# AD.net
KiCad netlist of a schematic drawn in Altium Designer
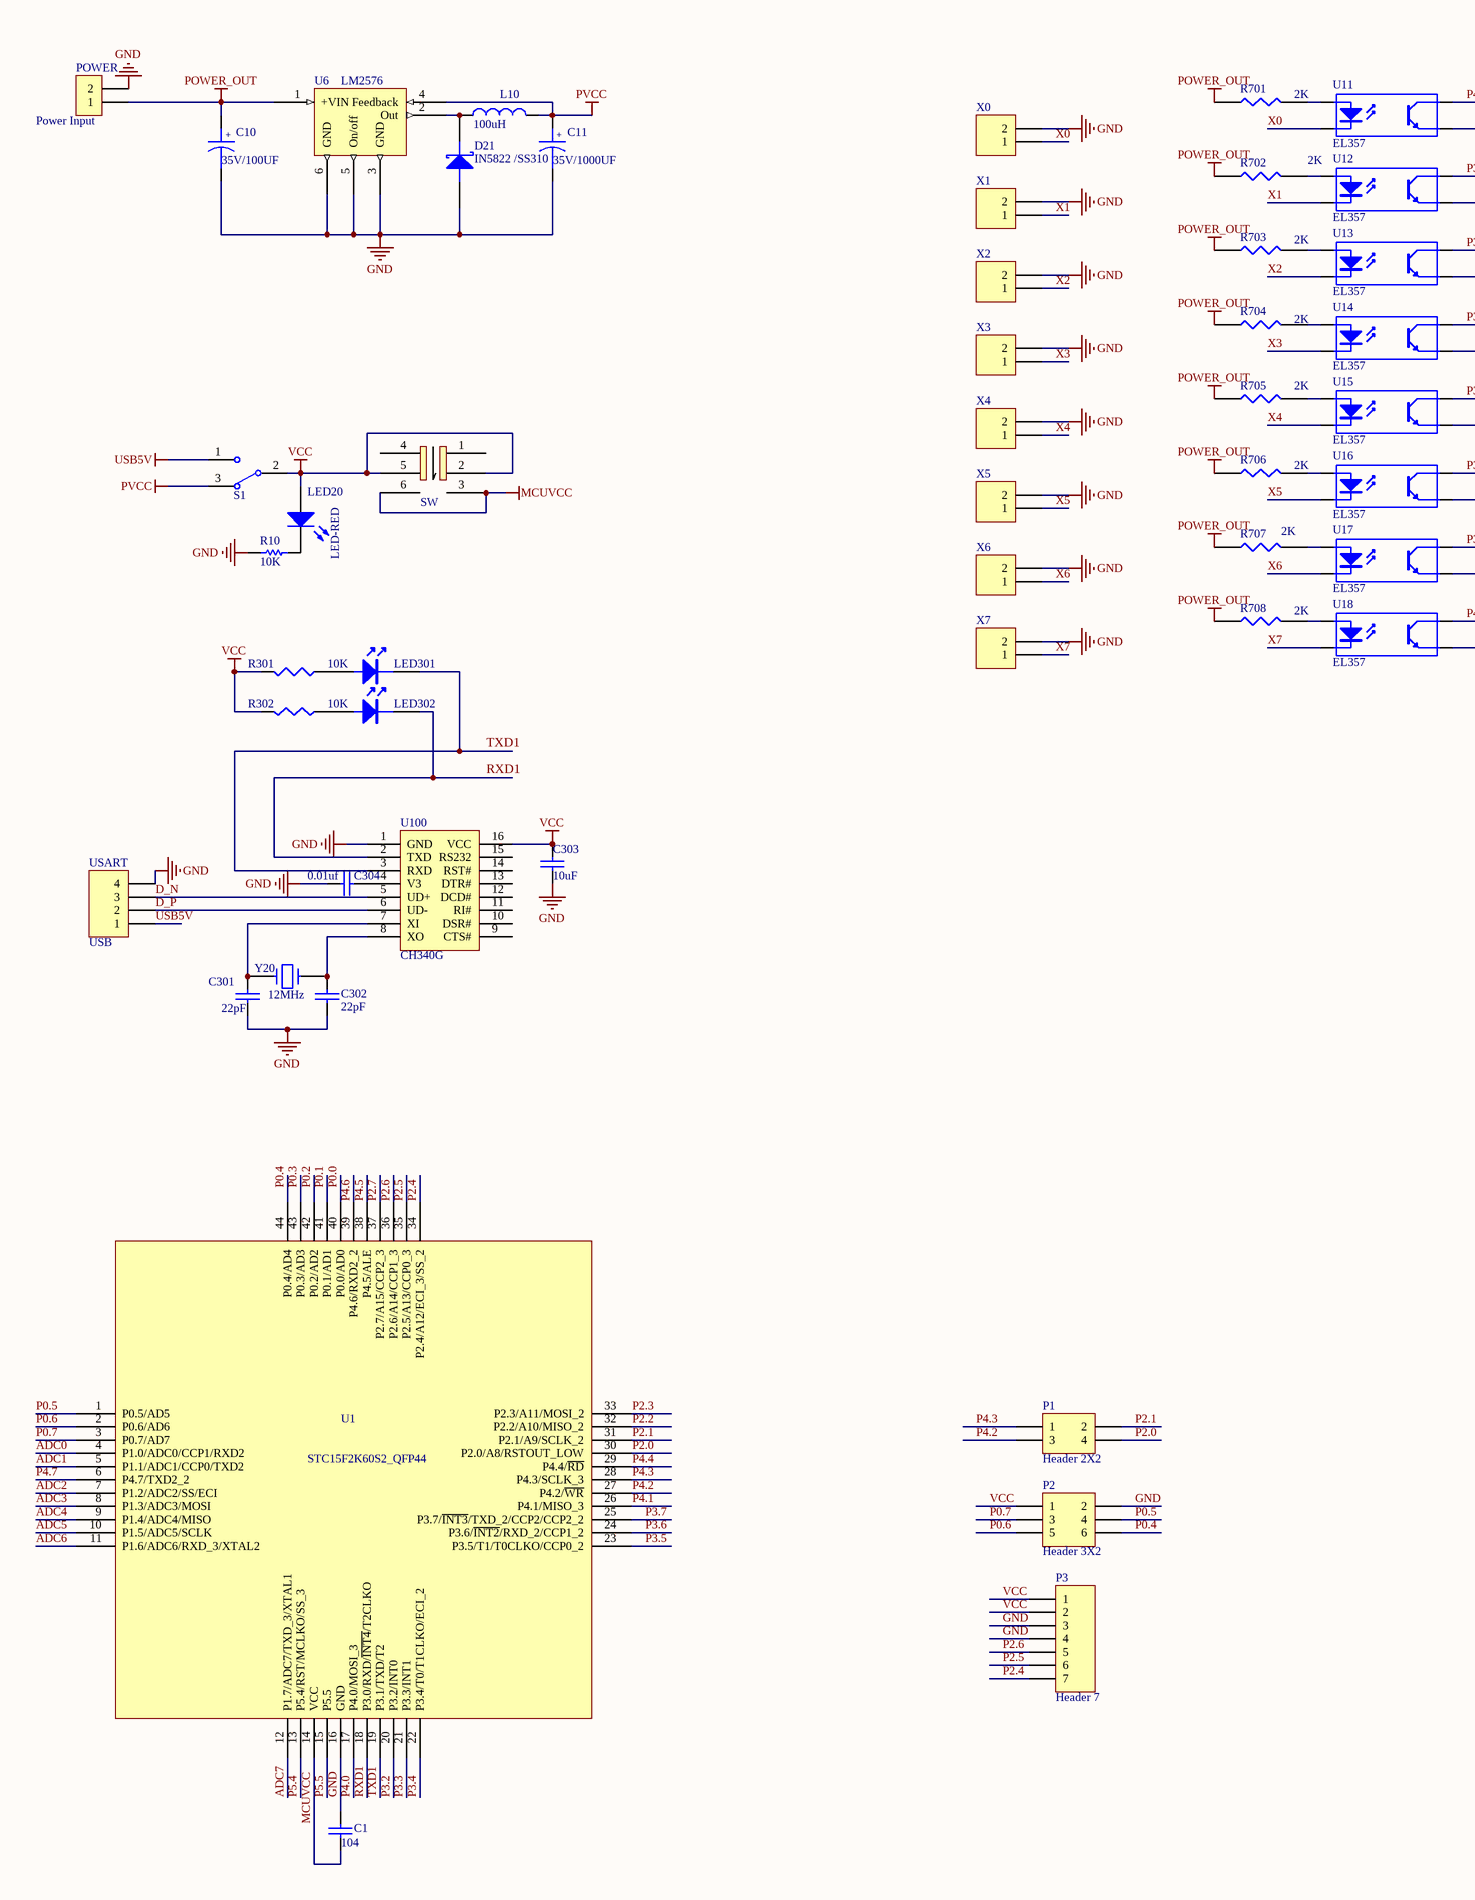
[diagram p0: AD.SchDoc, left]
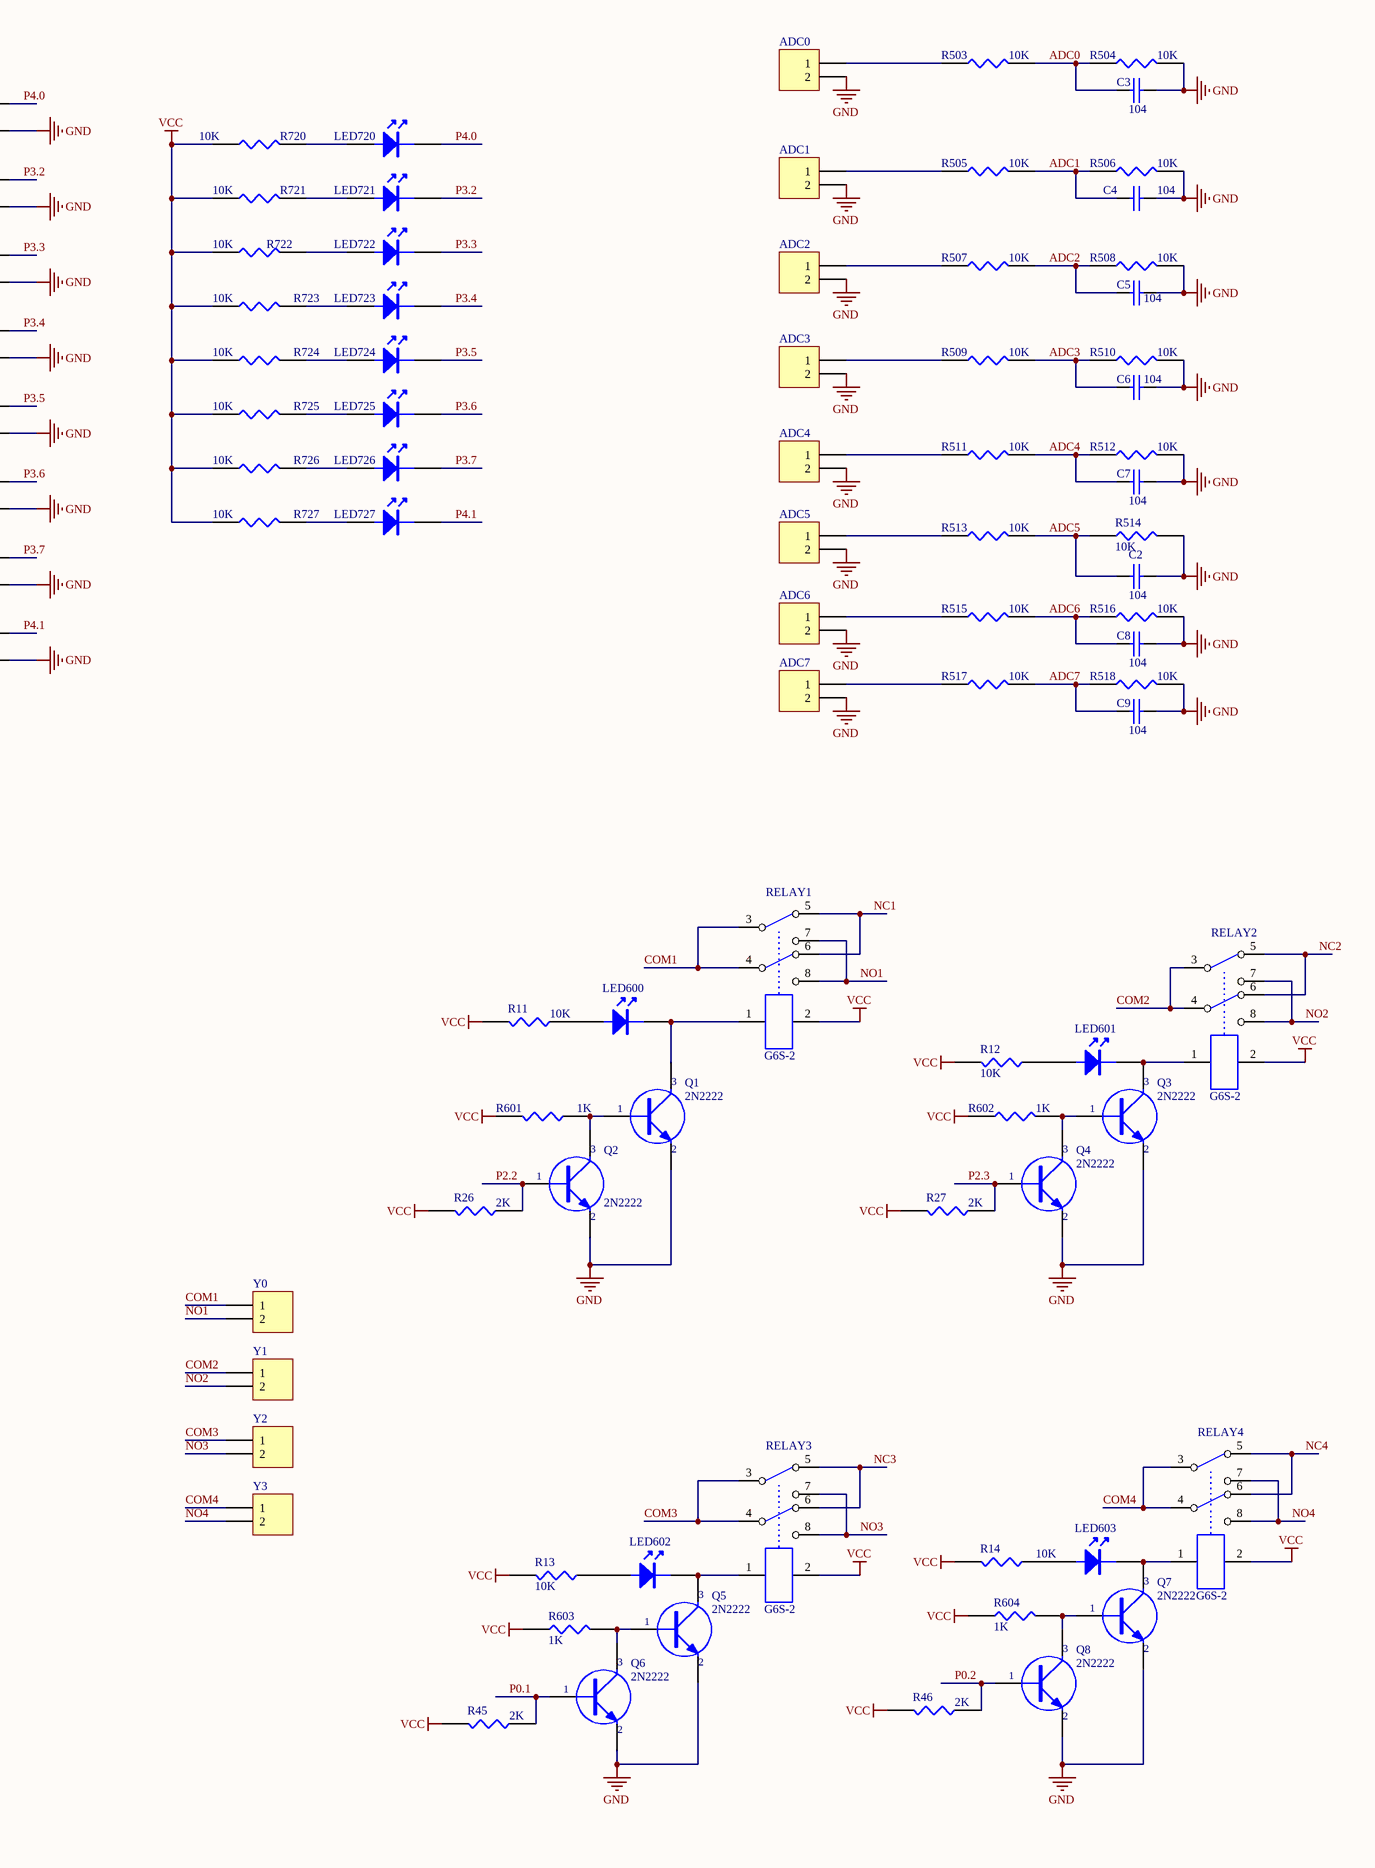
[diagram p1: AD.SchDoc, right]

(export (version "E")
  (design (tool "Eeschema 10.0.6"))
  (components
    (comp (ref "ADC0")
      (value "ADC")
      (footprint "CON2_1")
      (description "Header, 2-Pin")
      (fields (field (name "PUBLISHER") "Altium Limited"))
      (libsource (lib "") (part "Header 2_1"))
    )
    (comp (ref "ADC1")
      (value "ADC")
      (footprint "CON2_1")
      (description "Header, 2-Pin")
      (fields (field (name "PUBLISHER") "Altium Limited"))
      (libsource (lib "") (part "Header 2_1"))
    )
    (comp (ref "ADC2")
      (value "ADC")
      (footprint "CON2_1")
      (description "Header, 2-Pin")
      (fields (field (name "PUBLISHER") "Altium Limited"))
      (libsource (lib "") (part "Header 2_1"))
    )
    (comp (ref "ADC3")
      (value "ADC")
      (footprint "CON2_1")
      (description "Header, 2-Pin")
      (fields (field (name "PUBLISHER") "Altium Limited"))
      (libsource (lib "") (part "Header 2_1"))
    )
    (comp (ref "ADC4")
      (value "ADC")
      (footprint "CON2_1")
      (description "Header, 2-Pin")
      (fields (field (name "PUBLISHER") "Altium Limited"))
      (libsource (lib "") (part "Header 2_1"))
    )
    (comp (ref "ADC5")
      (value "ADC")
      (footprint "CON2_1")
      (description "Header, 2-Pin")
      (fields (field (name "PUBLISHER") "Altium Limited"))
      (libsource (lib "") (part "Header 2_1"))
    )
    (comp (ref "ADC6")
      (value "ADC")
      (footprint "CON2_1")
      (description "Header, 2-Pin")
      (fields (field (name "PUBLISHER") "Altium Limited"))
      (libsource (lib "") (part "Header 2_1"))
    )
    (comp (ref "ADC7")
      (value "ADC")
      (footprint "CON2_1")
      (description "Header, 2-Pin")
      (fields (field (name "PUBLISHER") "Altium Limited"))
      (libsource (lib "") (part "Header 2_1"))
    )
    (comp (ref "C1") (value "104") (footprint "C-0805") (libsource (lib "brante_zhou") (part "CAP1")))
    (comp (ref "C2") (value "104") (footprint "C-0805") (libsource (lib "brante_zhou") (part "CAP1")))
    (comp (ref "C3") (value "104") (footprint "C-0805") (libsource (lib "brante_zhou") (part "CAP1")))
    (comp (ref "C4") (value "104") (footprint "C-0805") (libsource (lib "brante_zhou") (part "CAP1")))
    (comp (ref "C5") (value "104") (footprint "C-0805") (libsource (lib "brante_zhou") (part "CAP1")))
    (comp (ref "C6") (value "104") (footprint "C-0805") (libsource (lib "brante_zhou") (part "CAP1")))
    (comp (ref "C7") (value "104") (footprint "C-0805") (libsource (lib "brante_zhou") (part "CAP1")))
    (comp (ref "C8") (value "104") (footprint "C-0805") (libsource (lib "brante_zhou") (part "CAP1")))
    (comp (ref "C9") (value "104") (footprint "C-0805") (libsource (lib "brante_zhou") (part "CAP1")))
    (comp (ref "C10") (value "35V/100UF") (footprint "RB") (libsource (lib "My_Schlib") (part "CAP2")))
    (comp (ref "C11") (value "35V/1000UF") (footprint "L-DIP") (libsource (lib "My_Schlib") (part "CAP2")))
    (comp (ref "C301") (value "22pF") (footprint "C-0805") (libsource (lib "My_Schlib") (part "CAP1")))
    (comp (ref "C302") (value "22pF") (footprint "C-0805") (libsource (lib "My_Schlib") (part "CAP1")))
    (comp (ref "C303") (value "10uF") (footprint "C-0805") (libsource (lib "My_Schlib") (part "CAP1")))
    (comp (ref "C304") (value "0.01uf") (footprint "C-0603") (libsource (lib "My_Schlib") (part "CAP1")))
    (comp (ref "D21")
      (value "IN5822 /SS310")
      (footprint "DO-214AC")
      (description "Schottky Diode")
      (libsource (lib "Miscellaneous Devices") (part "DIODE SCHOTTKY"))
    )
    (comp (ref "L10")
      (value "100uH")
      (footprint "L-DIP")
      (description "Inductor")
      (fields (field (name "PUBLISHER") "Altium Limited"))
      (libsource (lib "Miscellaneous Devices") (part "Inductor"))
    )
    (comp (ref "LED20")
      (value "LED-RED")
      (footprint "led-0805")
      (description "Typical INFRARED GaAs LED")
      (fields (field (name "PUBLISHER") "Altium Limited"))
      (libsource (lib "Miscellaneous Devices") (part "LED0"))
    )
    (comp (ref "LED301") (value "~") (footprint "LED-0805") (libsource (lib "*") (part "LED")))
    (comp (ref "LED302") (value "~") (footprint "LED-0805") (libsource (lib "*") (part "LED")))
    (comp (ref "LED600") (value "~") (footprint "LED-0805") (libsource (lib "brante_zhou") (part "LED")))
    (comp (ref "LED601") (value "~") (footprint "LED-0805") (libsource (lib "brante_zhou") (part "LED")))
    (comp (ref "LED602") (value "~") (footprint "LED-0805") (libsource (lib "brante_zhou") (part "LED")))
    (comp (ref "LED603") (value "~") (footprint "LED-0805") (libsource (lib "brante_zhou") (part "LED")))
    (comp (ref "LED720") (value "LED") (footprint "LED-0805") (libsource (lib "brante_zhou") (part "LED")))
    (comp (ref "LED721") (value "LED") (footprint "LED-0805") (libsource (lib "brante_zhou") (part "LED")))
    (comp (ref "LED722") (value "LED") (footprint "LED-0805") (libsource (lib "brante_zhou") (part "LED")))
    (comp (ref "LED723") (value "LED") (footprint "LED-0805") (libsource (lib "brante_zhou") (part "LED")))
    (comp (ref "LED724") (value "LED") (footprint "LED-0805") (libsource (lib "brante_zhou") (part "LED")))
    (comp (ref "LED725") (value "LED") (footprint "LED-0805") (libsource (lib "brante_zhou") (part "LED")))
    (comp (ref "LED726") (value "LED") (footprint "LED-0805") (libsource (lib "brante_zhou") (part "LED")))
    (comp (ref "LED727") (value "LED") (footprint "LED-0805") (libsource (lib "brante_zhou") (part "LED")))
    (comp (ref "P1")
      (value "Header 2X2")
      (footprint "HDR2X2")
      (description "Header, 2-Pin, Dual row")
      (fields (field (name "PUBLISHER") "Altium Limited"))
      (libsource (lib "Miscellaneous Connectors") (part "Header 2X2"))
    )
    (comp (ref "P2")
      (value "Header 3X2")
      (footprint "HDR2X3")
      (description "Header, 3-Pin, Dual row")
      (fields (field (name "PUBLISHER") "Altium Limited"))
      (libsource (lib "Miscellaneous Connectors") (part "Header 3X2"))
    )
    (comp (ref "P3")
      (value "Header 7")
      (footprint "HDR1X7")
      (description "Header, 7-Pin")
      (fields (field (name "PUBLISHER") "Altium Limited"))
      (libsource (lib "Miscellaneous Connectors") (part "Header 7"))
    )
    (comp (ref "POWER")
      (value "Power Input")
      (footprint "CON2_1")
      (libsource (lib "brante_zhou") (part "CON2"))
    )
    (comp (ref "Q1")
      (value "2N2222")
      (footprint "SOT23A")
      (description "NPN Transistor")
      (libsource (lib "My_Schlib") (part "NPN_S8050"))
    )
    (comp (ref "Q2")
      (value "2N2222")
      (footprint "SOT23A")
      (description "NPN Transistor")
      (libsource (lib "My_Schlib") (part "NPN_S8050"))
    )
    (comp (ref "Q3")
      (value "2N2222")
      (footprint "SOT23A")
      (description "NPN Transistor")
      (libsource (lib "My_Schlib") (part "NPN_S8050"))
    )
    (comp (ref "Q4")
      (value "2N2222")
      (footprint "SOT23A")
      (description "NPN Transistor")
      (libsource (lib "My_Schlib") (part "NPN_S8050"))
    )
    (comp (ref "Q5")
      (value "2N2222")
      (footprint "SOT23A")
      (description "NPN Transistor")
      (libsource (lib "My_Schlib") (part "NPN_S8050"))
    )
    (comp (ref "Q6")
      (value "2N2222")
      (footprint "SOT23A")
      (description "NPN Transistor")
      (libsource (lib "My_Schlib") (part "NPN_S8050"))
    )
    (comp (ref "Q7")
      (value "2N2222")
      (footprint "SOT23A")
      (description "NPN Transistor")
      (libsource (lib "My_Schlib") (part "NPN_S8050"))
    )
    (comp (ref "Q8")
      (value "2N2222")
      (footprint "SOT23A")
      (description "NPN Transistor")
      (libsource (lib "My_Schlib") (part "NPN_S8050"))
    )
    (comp (ref "R10")
      (value "10K")
      (footprint "R0805")
      (description "Semiconductor Resistor")
      (fields (field (name "PUBLISHER") "Altium Limited"))
      (libsource (lib "Miscellaneous Devices") (part "Res Semi"))
    )
    (comp (ref "R11") (value "10K") (footprint "R0805") (libsource (lib "brante_zhou") (part "RES")))
    (comp (ref "R12") (value "10K") (footprint "R0805") (libsource (lib "brante_zhou") (part "RES")))
    (comp (ref "R13") (value "10K") (footprint "R0805") (libsource (lib "brante_zhou") (part "RES")))
    (comp (ref "R14") (value "10K") (footprint "R0805") (libsource (lib "brante_zhou") (part "RES")))
    (comp (ref "R26") (value "2K") (footprint "R0805") (libsource (lib "brante_zhou") (part "RES")))
    (comp (ref "R27") (value "2K") (footprint "R0805") (libsource (lib "brante_zhou") (part "RES")))
    (comp (ref "R45") (value "2K") (footprint "R0805") (libsource (lib "brante_zhou") (part "RES")))
    (comp (ref "R46") (value "2K") (footprint "R0805") (libsource (lib "brante_zhou") (part "RES")))
    (comp (ref "R301")
      (value "10K")
      (footprint "R0805")
      (description "Resistor")
      (fields (field (name "PUBLISHER") "Altium Limited"))
      (libsource (lib "Miscellaneous Devices") (part "Res3"))
    )
    (comp (ref "R302")
      (value "10K")
      (footprint "R0805")
      (description "Resistor")
      (fields (field (name "PUBLISHER") "Altium Limited"))
      (libsource (lib "Miscellaneous Devices") (part "Res3"))
    )
    (comp (ref "R503") (value "10K") (footprint "R0805") (libsource (lib "brante_zhou") (part "RES")))
    (comp (ref "R504") (value "10K") (footprint "R0805") (libsource (lib "brante_zhou") (part "RES")))
    (comp (ref "R505") (value "10K") (footprint "R0805") (libsource (lib "brante_zhou") (part "RES")))
    (comp (ref "R506") (value "10K") (footprint "R0805") (libsource (lib "brante_zhou") (part "RES")))
    (comp (ref "R507") (value "10K") (footprint "R0805") (libsource (lib "brante_zhou") (part "RES")))
    (comp (ref "R508") (value "10K") (footprint "R0805") (libsource (lib "brante_zhou") (part "RES")))
    (comp (ref "R509") (value "10K") (footprint "R0805") (libsource (lib "brante_zhou") (part "RES")))
    (comp (ref "R510") (value "10K") (footprint "R0805") (libsource (lib "brante_zhou") (part "RES")))
    (comp (ref "R511") (value "10K") (footprint "R0805") (libsource (lib "brante_zhou") (part "RES")))
    (comp (ref "R512") (value "10K") (footprint "R0805") (libsource (lib "brante_zhou") (part "RES")))
    (comp (ref "R513") (value "10K") (footprint "R0805") (libsource (lib "brante_zhou") (part "RES")))
    (comp (ref "R514") (value "10K") (footprint "R0805") (libsource (lib "brante_zhou") (part "RES")))
    (comp (ref "R515") (value "10K") (footprint "R0805") (libsource (lib "brante_zhou") (part "RES")))
    (comp (ref "R516") (value "10K") (footprint "R0805") (libsource (lib "brante_zhou") (part "RES")))
    (comp (ref "R517") (value "10K") (footprint "R0805") (libsource (lib "brante_zhou") (part "RES")))
    (comp (ref "R518") (value "10K") (footprint "R0805") (libsource (lib "brante_zhou") (part "RES")))
    (comp (ref "R601") (value "1K") (footprint "R0805") (libsource (lib "brante_zhou") (part "RES")))
    (comp (ref "R602") (value "1K") (footprint "R0805") (libsource (lib "brante_zhou") (part "RES")))
    (comp (ref "R603") (value "1K") (footprint "R0805") (libsource (lib "brante_zhou") (part "RES")))
    (comp (ref "R604") (value "1K") (footprint "R0805") (libsource (lib "brante_zhou") (part "RES")))
    (comp (ref "R701") (value "2K") (footprint "R0805") (libsource (lib "brante_zhou") (part "RES")))
    (comp (ref "R702") (value "2K") (footprint "R0805") (libsource (lib "brante_zhou") (part "RES")))
    (comp (ref "R703") (value "2K") (footprint "R0805") (libsource (lib "brante_zhou") (part "RES")))
    (comp (ref "R704") (value "2K") (footprint "R0805") (libsource (lib "brante_zhou") (part "RES")))
    (comp (ref "R705") (value "2K") (footprint "R0805") (libsource (lib "brante_zhou") (part "RES")))
    (comp (ref "R706") (value "2K") (footprint "R0805") (libsource (lib "brante_zhou") (part "RES")))
    (comp (ref "R707") (value "2K") (footprint "R0805") (libsource (lib "brante_zhou") (part "RES")))
    (comp (ref "R708") (value "2K") (footprint "R0805") (libsource (lib "brante_zhou") (part "RES")))
    (comp (ref "R720") (value "10K") (footprint "R0805") (libsource (lib "brante_zhou") (part "RES")))
    (comp (ref "R721") (value "10K") (footprint "R0805") (libsource (lib "brante_zhou") (part "RES")))
    (comp (ref "R722") (value "10K") (footprint "R0805") (libsource (lib "brante_zhou") (part "RES")))
    (comp (ref "R723") (value "10K") (footprint "R0805") (libsource (lib "brante_zhou") (part "RES")))
    (comp (ref "R724") (value "10K") (footprint "R0805") (libsource (lib "brante_zhou") (part "RES")))
    (comp (ref "R725") (value "10K") (footprint "R0805") (libsource (lib "brante_zhou") (part "RES")))
    (comp (ref "R726") (value "10K") (footprint "R0805") (libsource (lib "brante_zhou") (part "RES")))
    (comp (ref "R727") (value "10K") (footprint "R0805") (libsource (lib "brante_zhou") (part "RES")))
    (comp (ref "RELAY1")
      (value "G6S-2")
      (footprint "G6S-2")
      (libsource (lib "My_Schlib") (part "RELAY-G6S-2"))
    )
    (comp (ref "RELAY2")
      (value "G6S-2")
      (footprint "G6S-2")
      (libsource (lib "My_Schlib") (part "RELAY-G6S-2"))
    )
    (comp (ref "RELAY3")
      (value "G6S-2")
      (footprint "G6S-2")
      (libsource (lib "My_Schlib") (part "RELAY-G6S-2"))
    )
    (comp (ref "RELAY4")
      (value "G6S-2")
      (footprint "G6S-2")
      (libsource (lib "My_Schlib") (part "RELAY-G6S-2"))
    )
    (comp (ref "S1")
      (value "SW-SPDT_2")
      (footprint "SW_1")
      (description "SPDT Subminiature Toggle Switch, Right Angle Mounting, Vertical Actuation")
      (fields (field (name "PUBLISHER") "Altium Limited"))
      (libsource (lib "My_Schlib") (part "SW-SPDT_2"))
    )
    (comp (ref "SW") (value "SW") (footprint "SW") (libsource (lib "RelayBoard") (part "SW")))
    (comp (ref "U1")
      (value "STC15F2K60S2_QFP44")
      (footprint "PQFP44")
      (libsource (lib "stcmcu_altium_lib") (part "STC15F2K60S2_QFP44"))
    )
    (comp (ref "U6") (value "LM2576") (footprint "LM2576") (libsource (lib "My_Schlib") (part "LM2576")))
    (comp (ref "U11")
      (value "EL357")
      (footprint "el357")
      (description "4-Pin Phototransistor Optocoupler")
      (fields (field (name "PUBLISHER") "Altium Limited"))
      (libsource (lib "My_Schlib") (part "Optoisolator"))
    )
    (comp (ref "U12")
      (value "EL357")
      (footprint "EL357")
      (description "4-Pin Phototransistor Optocoupler")
      (fields (field (name "PUBLISHER") "Altium Limited"))
      (libsource (lib "My_Schlib") (part "Optoisolator"))
    )
    (comp (ref "U13")
      (value "EL357")
      (footprint "EL357")
      (description "4-Pin Phototransistor Optocoupler")
      (fields (field (name "PUBLISHER") "Altium Limited"))
      (libsource (lib "My_Schlib") (part "Optoisolator"))
    )
    (comp (ref "U14")
      (value "EL357")
      (footprint "EL357")
      (description "4-Pin Phototransistor Optocoupler")
      (fields (field (name "PUBLISHER") "Altium Limited"))
      (libsource (lib "My_Schlib") (part "Optoisolator"))
    )
    (comp (ref "U15")
      (value "EL357")
      (footprint "EL357")
      (description "4-Pin Phototransistor Optocoupler")
      (fields (field (name "PUBLISHER") "Altium Limited"))
      (libsource (lib "My_Schlib") (part "Optoisolator"))
    )
    (comp (ref "U16")
      (value "EL357")
      (footprint "EL357")
      (description "4-Pin Phototransistor Optocoupler")
      (fields (field (name "PUBLISHER") "Altium Limited"))
      (libsource (lib "My_Schlib") (part "Optoisolator"))
    )
    (comp (ref "U17")
      (value "EL357")
      (footprint "EL357")
      (description "4-Pin Phototransistor Optocoupler")
      (fields (field (name "PUBLISHER") "Altium Limited"))
      (libsource (lib "My_Schlib") (part "Optoisolator"))
    )
    (comp (ref "U18")
      (value "EL357")
      (footprint "EL357")
      (description "4-Pin Phototransistor Optocoupler")
      (fields (field (name "PUBLISHER") "Altium Limited"))
      (libsource (lib "My_Schlib") (part "Optoisolator"))
    )
    (comp (ref "U100") (value "CH340G") (footprint "CH340G") (libsource (lib "My_Schlib") (part "CH340G")))
    (comp (ref "USART")
      (value "USB")
      (footprint "USB2.0_A")
      (description "Header, 4-Pin")
      (fields (field (name "PUBLISHER") "Altium Limited"))
      (libsource (lib "Miscellaneous Connectors") (part "Header 4"))
    )
    (comp (ref "X0")
      (value "XH2.54")
      (footprint "con2_1")
      (description "Header, 2-Pin")
      (fields (field (name "PUBLISHER") "Altium Limited"))
      (libsource (lib "") (part "Header 2_2"))
    )
    (comp (ref "X1")
      (value "XH2.54")
      (footprint "con2_1")
      (description "Header, 2-Pin")
      (fields (field (name "PUBLISHER") "Altium Limited"))
      (libsource (lib "") (part "Header 2_2"))
    )
    (comp (ref "X2")
      (value "XH2.54")
      (footprint "con2_1")
      (description "Header, 2-Pin")
      (fields (field (name "PUBLISHER") "Altium Limited"))
      (libsource (lib "") (part "Header 2_2"))
    )
    (comp (ref "X3")
      (value "XH2.54")
      (footprint "con2_1")
      (description "Header, 2-Pin")
      (fields (field (name "PUBLISHER") "Altium Limited"))
      (libsource (lib "") (part "Header 2_2"))
    )
    (comp (ref "X4")
      (value "XH2.54")
      (footprint "con2_1")
      (description "Header, 2-Pin")
      (fields (field (name "PUBLISHER") "Altium Limited"))
      (libsource (lib "") (part "Header 2_2"))
    )
    (comp (ref "X5")
      (value "XH2.54")
      (footprint "con2_1")
      (description "Header, 2-Pin")
      (fields (field (name "PUBLISHER") "Altium Limited"))
      (libsource (lib "") (part "Header 2_2"))
    )
    (comp (ref "X6")
      (value "XH2.54")
      (footprint "con2_1")
      (description "Header, 2-Pin")
      (fields (field (name "PUBLISHER") "Altium Limited"))
      (libsource (lib "") (part "Header 2_2"))
    )
    (comp (ref "X7")
      (value "XH2.54")
      (footprint "con2_1")
      (description "Header, 2-Pin")
      (fields (field (name "PUBLISHER") "Altium Limited"))
      (libsource (lib "") (part "Header 2_2"))
    )
    (comp (ref "Y0")
      (value "Header 2")
      (footprint "CON2_1")
      (description "Header, 2-Pin")
      (fields (field (name "PUBLISHER") "Altium Limited"))
      (libsource (lib "Miscellaneous Connectors") (part "Header 2"))
    )
    (comp (ref "Y1")
      (value "Header 2")
      (footprint "CON2_1")
      (description "Header, 2-Pin")
      (fields (field (name "PUBLISHER") "Altium Limited"))
      (libsource (lib "Miscellaneous Connectors") (part "Header 2"))
    )
    (comp (ref "Y2")
      (value "Header 2")
      (footprint "CON2_1")
      (description "Header, 2-Pin")
      (fields (field (name "PUBLISHER") "Altium Limited"))
      (libsource (lib "Miscellaneous Connectors") (part "Header 2"))
    )
    (comp (ref "Y3")
      (value "Header 2")
      (footprint "CON2_1")
      (description "Header, 2-Pin")
      (fields (field (name "PUBLISHER") "Altium Limited"))
      (libsource (lib "Miscellaneous Connectors") (part "Header 2"))
    )
    (comp (ref "Y20")
      (value "12MHz")
      (footprint "XTAL1")
      (description "Crystal")
      (libsource (lib "My_Schlib") (part "CRYSTAL"))
    )
  )
  (nets
    (net (code "1") (name "/ADC0") (class "Default")
      (node (ref "C3") (pin "2") (pinfunction "2_2") (pintype "passive"))
      (node (ref "R503") (pin "2") (pinfunction "2_2") (pintype "passive"))
      (node (ref "R504") (pin "1") (pinfunction "1_1") (pintype "passive"))
      (node (ref "U1") (pin "4") (pinfunction "P1.0/ADC0/CCP1/RXD2_4") (pintype "passive"))
    )
    (net (code "2") (name "/ADC1") (class "Default")
      (node (ref "C4") (pin "2") (pinfunction "2_2") (pintype "passive"))
      (node (ref "R505") (pin "2") (pinfunction "2_2") (pintype "passive"))
      (node (ref "R506") (pin "1") (pinfunction "1_1") (pintype "passive"))
      (node (ref "U1") (pin "5") (pinfunction "P1.1/ADC1/CCP0/TXD2_5") (pintype "passive"))
    )
    (net (code "3") (name "/ADC2") (class "Default")
      (node (ref "C5") (pin "2") (pinfunction "2_2") (pintype "passive"))
      (node (ref "R507") (pin "2") (pinfunction "2_2") (pintype "passive"))
      (node (ref "R508") (pin "1") (pinfunction "1_1") (pintype "passive"))
      (node (ref "U1") (pin "7") (pinfunction "P1.2/ADC2/SS/ECI_7") (pintype "passive"))
    )
    (net (code "4") (name "/ADC3") (class "Default")
      (node (ref "C6") (pin "2") (pinfunction "2_2") (pintype "passive"))
      (node (ref "R509") (pin "2") (pinfunction "2_2") (pintype "passive"))
      (node (ref "R510") (pin "1") (pinfunction "1_1") (pintype "passive"))
      (node (ref "U1") (pin "8") (pinfunction "P1.3/ADC3/MOSI_8") (pintype "passive"))
    )
    (net (code "5") (name "/ADC4") (class "Default")
      (node (ref "C7") (pin "2") (pinfunction "2_2") (pintype "passive"))
      (node (ref "R511") (pin "2") (pinfunction "2_2") (pintype "passive"))
      (node (ref "R512") (pin "1") (pinfunction "1_1") (pintype "passive"))
      (node (ref "U1") (pin "9") (pinfunction "P1.4/ADC4/MISO_9") (pintype "passive"))
    )
    (net (code "6") (name "/ADC5") (class "Default")
      (node (ref "C2") (pin "1") (pinfunction "1_1") (pintype "passive"))
      (node (ref "R513") (pin "2") (pinfunction "2_2") (pintype "passive"))
      (node (ref "R514") (pin "1") (pinfunction "1_1") (pintype "passive"))
      (node (ref "U1") (pin "10") (pinfunction "P1.5/ADC5/SCLK_10") (pintype "passive"))
    )
    (net (code "7") (name "/ADC6") (class "Default")
      (node (ref "C8") (pin "2") (pinfunction "2_2") (pintype "passive"))
      (node (ref "R515") (pin "2") (pinfunction "2_2") (pintype "passive"))
      (node (ref "R516") (pin "1") (pinfunction "1_1") (pintype "passive"))
      (node (ref "U1") (pin "11") (pinfunction "P1.6/ADC6/RXD_3/XTAL2_11") (pintype "passive"))
    )
    (net (code "8") (name "/ADC7") (class "Default")
      (node (ref "C9") (pin "2") (pinfunction "2_2") (pintype "passive"))
      (node (ref "R517") (pin "2") (pinfunction "2_2") (pintype "passive"))
      (node (ref "R518") (pin "1") (pinfunction "1_1") (pintype "passive"))
      (node (ref "U1") (pin "12") (pinfunction "P1.7/ADC7/TXD_3/XTAL1_12") (pintype "passive"))
    )
    (net (code "9") (name "/COM1") (class "Default")
      (node (ref "RELAY1") (pin "3") (pinfunction "3_3") (pintype "passive"))
      (node (ref "RELAY1") (pin "4") (pinfunction "4_4") (pintype "passive"))
      (node (ref "Y0") (pin "1") (pinfunction "1_1") (pintype "passive"))
    )
    (net (code "10") (name "/COM2") (class "Default")
      (node (ref "RELAY2") (pin "3") (pinfunction "3_3") (pintype "passive"))
      (node (ref "RELAY2") (pin "4") (pinfunction "4_4") (pintype "passive"))
      (node (ref "Y1") (pin "1") (pinfunction "1_1") (pintype "passive"))
    )
    (net (code "11") (name "/COM3") (class "Default")
      (node (ref "RELAY3") (pin "3") (pinfunction "3_3") (pintype "passive"))
      (node (ref "RELAY3") (pin "4") (pinfunction "4_4") (pintype "passive"))
      (node (ref "Y2") (pin "1") (pinfunction "1_1") (pintype "passive"))
    )
    (net (code "12") (name "/COM4") (class "Default")
      (node (ref "RELAY4") (pin "3") (pinfunction "3_3") (pintype "passive"))
      (node (ref "RELAY4") (pin "4") (pinfunction "4_4") (pintype "passive"))
      (node (ref "Y3") (pin "1") (pinfunction "1_1") (pintype "passive"))
    )
    (net (code "13") (name "/D_N") (class "Default")
      (node (ref "U100") (pin "5") (pinfunction "UD+_5") (pintype "passive"))
      (node (ref "USART") (pin "3") (pinfunction "3_3") (pintype "passive"))
    )
    (net (code "14") (name "/D_P") (class "Default")
      (node (ref "U100") (pin "6") (pinfunction "UD-_6") (pintype "passive"))
      (node (ref "USART") (pin "2") (pinfunction "2_2") (pintype "passive"))
    )
    (net (code "15") (name "/NC1") (class "Default")
      (node (ref "RELAY1") (pin "5") (pinfunction "5_5") (pintype "passive"))
      (node (ref "RELAY1") (pin "6") (pinfunction "6_6") (pintype "passive"))
    )
    (net (code "16") (name "/NC2") (class "Default")
      (node (ref "RELAY2") (pin "5") (pinfunction "5_5") (pintype "passive"))
      (node (ref "RELAY2") (pin "6") (pinfunction "6_6") (pintype "passive"))
    )
    (net (code "17") (name "/NC3") (class "Default")
      (node (ref "RELAY3") (pin "5") (pinfunction "5_5") (pintype "passive"))
      (node (ref "RELAY3") (pin "6") (pinfunction "6_6") (pintype "passive"))
    )
    (net (code "18") (name "/NC4") (class "Default")
      (node (ref "RELAY4") (pin "5") (pinfunction "5_5") (pintype "passive"))
      (node (ref "RELAY4") (pin "6") (pinfunction "6_6") (pintype "passive"))
    )
    (net (code "19") (name "/NO1") (class "Default")
      (node (ref "RELAY1") (pin "7") (pinfunction "7_7") (pintype "passive"))
      (node (ref "RELAY1") (pin "8") (pinfunction "8_8") (pintype "passive"))
      (node (ref "Y0") (pin "2") (pinfunction "2_2") (pintype "passive"))
    )
    (net (code "20") (name "/NO2") (class "Default")
      (node (ref "RELAY2") (pin "7") (pinfunction "7_7") (pintype "passive"))
      (node (ref "RELAY2") (pin "8") (pinfunction "8_8") (pintype "passive"))
      (node (ref "Y1") (pin "2") (pinfunction "2_2") (pintype "passive"))
    )
    (net (code "21") (name "/NO3") (class "Default")
      (node (ref "RELAY3") (pin "7") (pinfunction "7_7") (pintype "passive"))
      (node (ref "RELAY3") (pin "8") (pinfunction "8_8") (pintype "passive"))
      (node (ref "Y2") (pin "2") (pinfunction "2_2") (pintype "passive"))
    )
    (net (code "22") (name "/NO4") (class "Default")
      (node (ref "RELAY4") (pin "7") (pinfunction "7_7") (pintype "passive"))
      (node (ref "RELAY4") (pin "8") (pinfunction "8_8") (pintype "passive"))
      (node (ref "Y3") (pin "2") (pinfunction "2_2") (pintype "passive"))
    )
    (net (code "23") (name "/P0.0") (class "Default")
      (node (ref "U1") (pin "40") (pinfunction "P0.0/AD0_40") (pintype "passive"))
    )
    (net (code "24") (name "/P0.1") (class "Default")
      (node (ref "Q6") (pin "1") (pinfunction "B_1") (pintype "passive"))
      (node (ref "R45") (pin "1") (pinfunction "1_1") (pintype "passive"))
      (node (ref "U1") (pin "41") (pinfunction "P0.1/AD1_41") (pintype "passive"))
    )
    (net (code "25") (name "/P0.2") (class "Default")
      (node (ref "Q8") (pin "1") (pinfunction "B_1") (pintype "passive"))
      (node (ref "R46") (pin "1") (pinfunction "1_1") (pintype "passive"))
      (node (ref "U1") (pin "42") (pinfunction "P0.2/AD2_42") (pintype "passive"))
    )
    (net (code "26") (name "/P0.3") (class "Default")
      (node (ref "U1") (pin "43") (pinfunction "P0.3/AD3_43") (pintype "passive"))
    )
    (net (code "27") (name "/P0.4") (class "Default")
      (node (ref "P2") (pin "6") (pinfunction "6_6") (pintype "passive"))
      (node (ref "U1") (pin "44") (pinfunction "P0.4/AD4_44") (pintype "passive"))
    )
    (net (code "28") (name "/P0.5") (class "Default")
      (node (ref "P2") (pin "4") (pinfunction "4_4") (pintype "passive"))
      (node (ref "U1") (pin "1") (pinfunction "P0.5/AD5_1") (pintype "passive"))
    )
    (net (code "29") (name "/P0.6") (class "Default")
      (node (ref "P2") (pin "5") (pinfunction "5_5") (pintype "passive"))
      (node (ref "U1") (pin "2") (pinfunction "P0.6/AD6_2") (pintype "passive"))
    )
    (net (code "30") (name "/P0.7") (class "Default")
      (node (ref "P2") (pin "3") (pinfunction "3_3") (pintype "passive"))
      (node (ref "U1") (pin "3") (pinfunction "P0.7/AD7_3") (pintype "passive"))
    )
    (net (code "31") (name "/P2.0") (class "Default")
      (node (ref "P1") (pin "4") (pinfunction "4_4") (pintype "passive"))
      (node (ref "U1") (pin "30") (pinfunction "P2.0/A8/RSTOUT_LOW_30") (pintype "passive"))
    )
    (net (code "32") (name "/P2.1") (class "Default")
      (node (ref "P1") (pin "2") (pinfunction "2_2") (pintype "passive"))
      (node (ref "U1") (pin "31") (pinfunction "P2.1/A9/SCLK_2_31") (pintype "passive"))
    )
    (net (code "33") (name "/P2.2") (class "Default")
      (node (ref "Q2") (pin "1") (pinfunction "B_1") (pintype "passive"))
      (node (ref "R26") (pin "1") (pinfunction "1_1") (pintype "passive"))
      (node (ref "U1") (pin "32") (pinfunction "P2.2/A10/MISO_2_32") (pintype "passive"))
    )
    (net (code "34") (name "/P2.3") (class "Default")
      (node (ref "Q4") (pin "1") (pinfunction "B_1") (pintype "passive"))
      (node (ref "R27") (pin "1") (pinfunction "1_1") (pintype "passive"))
      (node (ref "U1") (pin "33") (pinfunction "P2.3/A11/MOSI_2_33") (pintype "passive"))
    )
    (net (code "35") (name "/P2.4") (class "Default")
      (node (ref "P3") (pin "7") (pinfunction "7_7") (pintype "passive"))
      (node (ref "U1") (pin "34") (pinfunction "P2.4/A12/ECI_3/SS_2_34") (pintype "passive"))
    )
    (net (code "36") (name "/P2.5") (class "Default")
      (node (ref "P3") (pin "6") (pinfunction "6_6") (pintype "passive"))
      (node (ref "U1") (pin "35") (pinfunction "P2.5/A13/CCP0_3_35") (pintype "passive"))
    )
    (net (code "37") (name "/P2.6") (class "Default")
      (node (ref "P3") (pin "5") (pinfunction "5_5") (pintype "passive"))
      (node (ref "U1") (pin "36") (pinfunction "P2.6/A14/CCP1_3_36") (pintype "passive"))
    )
    (net (code "38") (name "/P2.7") (class "Default")
      (node (ref "U1") (pin "37") (pinfunction "P2.7/A15/CCP2_3_37") (pintype "passive"))
    )
    (net (code "39") (name "/P3.2") (class "Default")
      (node (ref "LED721") (pin "2") (pinfunction "2_2") (pintype "passive"))
      (node (ref "U1") (pin "20") (pinfunction "P3.2/INT0_20") (pintype "passive"))
      (node (ref "U12") (pin "4") (pinfunction "C_4") (pintype "passive"))
    )
    (net (code "40") (name "/P3.3") (class "Default")
      (node (ref "LED722") (pin "2") (pinfunction "2_2") (pintype "passive"))
      (node (ref "U1") (pin "21") (pinfunction "P3.3/INT1_21") (pintype "passive"))
      (node (ref "U13") (pin "4") (pinfunction "C_4") (pintype "passive"))
    )
    (net (code "41") (name "/P3.4") (class "Default")
      (node (ref "LED723") (pin "2") (pinfunction "2_2") (pintype "passive"))
      (node (ref "U1") (pin "22") (pinfunction "P3.4/T0/T1CLKO/ECI_2_22") (pintype "passive"))
      (node (ref "U14") (pin "4") (pinfunction "C_4") (pintype "passive"))
    )
    (net (code "42") (name "/P3.5") (class "Default")
      (node (ref "LED724") (pin "2") (pinfunction "2_2") (pintype "passive"))
      (node (ref "U1") (pin "23") (pinfunction "P3.5/T1/T0CLKO/CCP0_2_23") (pintype "passive"))
      (node (ref "U15") (pin "4") (pinfunction "C_4") (pintype "passive"))
    )
    (net (code "43") (name "/P3.6") (class "Default")
      (node (ref "LED725") (pin "2") (pinfunction "2_2") (pintype "passive"))
      (node (ref "U1") (pin "24") (pinfunction "P3.6/~{INT2}/RXD_2/CCP1_2_24") (pintype "passive"))
      (node (ref "U16") (pin "4") (pinfunction "C_4") (pintype "passive"))
    )
    (net (code "44") (name "/P3.7") (class "Default")
      (node (ref "LED726") (pin "2") (pinfunction "2_2") (pintype "passive"))
      (node (ref "U1") (pin "25") (pinfunction "P3.7/~{INT3}/TXD_2/CCP2/CCP2_2_25") (pintype "passive"))
      (node (ref "U17") (pin "4") (pinfunction "C_4") (pintype "passive"))
    )
    (net (code "45") (name "/P4.0") (class "Default")
      (node (ref "LED720") (pin "2") (pinfunction "2_2") (pintype "passive"))
      (node (ref "U1") (pin "17") (pinfunction "P4.0/MOSI_3_17") (pintype "passive"))
      (node (ref "U11") (pin "4") (pinfunction "C_4") (pintype "passive"))
    )
    (net (code "46") (name "/P4.1") (class "Default")
      (node (ref "LED727") (pin "2") (pinfunction "2_2") (pintype "passive"))
      (node (ref "U1") (pin "26") (pinfunction "P4.1/MISO_3_26") (pintype "passive"))
      (node (ref "U18") (pin "4") (pinfunction "C_4") (pintype "passive"))
    )
    (net (code "47") (name "/P4.2") (class "Default")
      (node (ref "P1") (pin "3") (pinfunction "3_3") (pintype "passive"))
      (node (ref "U1") (pin "27") (pinfunction "P4.2/~{WR}_27") (pintype "passive"))
    )
    (net (code "48") (name "/P4.3") (class "Default")
      (node (ref "P1") (pin "1") (pinfunction "1_1") (pintype "passive"))
      (node (ref "U1") (pin "28") (pinfunction "P4.3/SCLK_3_28") (pintype "passive"))
    )
    (net (code "49") (name "/P4.4") (class "Default")
      (node (ref "U1") (pin "29") (pinfunction "P4.4/~{RD}_29") (pintype "passive"))
    )
    (net (code "50") (name "/P4.5") (class "Default")
      (node (ref "U1") (pin "38") (pinfunction "P4.5/ALE_38") (pintype "passive"))
    )
    (net (code "51") (name "/P4.6") (class "Default")
      (node (ref "U1") (pin "39") (pinfunction "P4.6/RXD2_2_39") (pintype "passive"))
    )
    (net (code "52") (name "/P4.7") (class "Default")
      (node (ref "U1") (pin "6") (pinfunction "P4.7/TXD2_2_6") (pintype "passive"))
    )
    (net (code "53") (name "/P5.4") (class "Default")
      (node (ref "U1") (pin "13") (pinfunction "P5.4/RST/MCLKO/SS_3_13") (pintype "passive"))
    )
    (net (code "54") (name "/P5.5") (class "Default")
      (node (ref "U1") (pin "15") (pinfunction "P5.5_15") (pintype "passive"))
    )
    (net (code "55") (name "/RXD1") (class "Default")
      (node (ref "LED302") (pin "2") (pinfunction "2_2") (pintype "passive"))
      (node (ref "U1") (pin "18") (pinfunction "P3.0/RXD/~{INT4}/T2CLKO_18") (pintype "passive"))
      (node (ref "U100") (pin "2") (pinfunction "TXD_2") (pintype "passive"))
    )
    (net (code "56") (name "/TXD1") (class "Default")
      (node (ref "LED301") (pin "2") (pinfunction "2_2") (pintype "passive"))
      (node (ref "U1") (pin "19") (pinfunction "P3.1/TXD/T2_19") (pintype "passive"))
      (node (ref "U100") (pin "3") (pinfunction "RXD_3") (pintype "passive"))
    )
    (net (code "57") (name "/X0") (class "Default")
      (node (ref "U11") (pin "2") (pinfunction "K_2") (pintype "passive"))
      (node (ref "X0") (pin "1") (pinfunction "1_1") (pintype "passive"))
    )
    (net (code "58") (name "/X1") (class "Default")
      (node (ref "U12") (pin "2") (pinfunction "K_2") (pintype "passive"))
      (node (ref "X1") (pin "1") (pinfunction "1_1") (pintype "passive"))
    )
    (net (code "59") (name "/X2") (class "Default")
      (node (ref "U13") (pin "2") (pinfunction "K_2") (pintype "passive"))
      (node (ref "X2") (pin "1") (pinfunction "1_1") (pintype "passive"))
    )
    (net (code "60") (name "/X3") (class "Default")
      (node (ref "U14") (pin "2") (pinfunction "K_2") (pintype "passive"))
      (node (ref "X3") (pin "1") (pinfunction "1_1") (pintype "passive"))
    )
    (net (code "61") (name "/X4") (class "Default")
      (node (ref "U15") (pin "2") (pinfunction "K_2") (pintype "passive"))
      (node (ref "X4") (pin "1") (pinfunction "1_1") (pintype "passive"))
    )
    (net (code "62") (name "/X5") (class "Default")
      (node (ref "U16") (pin "2") (pinfunction "K_2") (pintype "passive"))
      (node (ref "X5") (pin "1") (pinfunction "1_1") (pintype "passive"))
    )
    (net (code "63") (name "/X6") (class "Default")
      (node (ref "U17") (pin "2") (pinfunction "K_2") (pintype "passive"))
      (node (ref "X6") (pin "1") (pinfunction "1_1") (pintype "passive"))
    )
    (net (code "64") (name "/X7") (class "Default")
      (node (ref "U18") (pin "2") (pinfunction "K_2") (pintype "passive"))
      (node (ref "X7") (pin "1") (pinfunction "1_1") (pintype "passive"))
    )
    (net (code "65") (name "GND") (class "Default")
      (node (ref "ADC0") (pin "2") (pinfunction "2_2") (pintype "passive"))
      (node (ref "ADC1") (pin "2") (pinfunction "2_2") (pintype "passive"))
      (node (ref "ADC2") (pin "2") (pinfunction "2_2") (pintype "passive"))
      (node (ref "ADC3") (pin "2") (pinfunction "2_2") (pintype "passive"))
      (node (ref "ADC4") (pin "2") (pinfunction "2_2") (pintype "passive"))
      (node (ref "ADC5") (pin "2") (pinfunction "2_2") (pintype "passive"))
      (node (ref "ADC6") (pin "2") (pinfunction "2_2") (pintype "passive"))
      (node (ref "ADC7") (pin "2") (pinfunction "2_2") (pintype "passive"))
      (node (ref "C1") (pin "2") (pinfunction "2_2") (pintype "passive"))
      (node (ref "C10") (pin "2") (pinfunction "2_2") (pintype "passive"))
      (node (ref "C11") (pin "2") (pinfunction "2_2") (pintype "passive"))
      (node (ref "C2") (pin "2") (pinfunction "2_2") (pintype "passive"))
      (node (ref "C3") (pin "1") (pinfunction "1_1") (pintype "passive"))
      (node (ref "C301") (pin "2") (pinfunction "2_2") (pintype "passive"))
      (node (ref "C302") (pin "2") (pinfunction "2_2") (pintype "passive"))
      (node (ref "C303") (pin "2") (pinfunction "2_2") (pintype "passive"))
      (node (ref "C304") (pin "1") (pinfunction "1_1") (pintype "passive"))
      (node (ref "C4") (pin "1") (pinfunction "1_1") (pintype "passive"))
      (node (ref "C5") (pin "1") (pinfunction "1_1") (pintype "passive"))
      (node (ref "C6") (pin "1") (pinfunction "1_1") (pintype "passive"))
      (node (ref "C7") (pin "1") (pinfunction "1_1") (pintype "passive"))
      (node (ref "C8") (pin "1") (pinfunction "1_1") (pintype "passive"))
      (node (ref "C9") (pin "1") (pinfunction "1_1") (pintype "passive"))
      (node (ref "D21") (pin "1") (pinfunction "A_1") (pintype "passive"))
      (node (ref "P2") (pin "2") (pinfunction "2_2") (pintype "passive"))
      (node (ref "P3") (pin "3") (pinfunction "3_3") (pintype "passive"))
      (node (ref "P3") (pin "4") (pinfunction "4_4") (pintype "passive"))
      (node (ref "POWER") (pin "2") (pinfunction "2_2") (pintype "passive"))
      (node (ref "Q1") (pin "2") (pinfunction "E_2") (pintype "passive"))
      (node (ref "Q2") (pin "2") (pinfunction "E_2") (pintype "passive"))
      (node (ref "Q3") (pin "2") (pinfunction "E_2") (pintype "passive"))
      (node (ref "Q4") (pin "2") (pinfunction "E_2") (pintype "passive"))
      (node (ref "Q5") (pin "2") (pinfunction "E_2") (pintype "passive"))
      (node (ref "Q6") (pin "2") (pinfunction "E_2") (pintype "passive"))
      (node (ref "Q7") (pin "2") (pinfunction "E_2") (pintype "passive"))
      (node (ref "Q8") (pin "2") (pinfunction "E_2") (pintype "passive"))
      (node (ref "R10") (pin "1") (pinfunction "1_1") (pintype "passive"))
      (node (ref "R504") (pin "2") (pinfunction "2_2") (pintype "passive"))
      (node (ref "R506") (pin "2") (pinfunction "2_2") (pintype "passive"))
      (node (ref "R508") (pin "2") (pinfunction "2_2") (pintype "passive"))
      (node (ref "R510") (pin "2") (pinfunction "2_2") (pintype "passive"))
      (node (ref "R512") (pin "2") (pinfunction "2_2") (pintype "passive"))
      (node (ref "R514") (pin "2") (pinfunction "2_2") (pintype "passive"))
      (node (ref "R516") (pin "2") (pinfunction "2_2") (pintype "passive"))
      (node (ref "R518") (pin "2") (pinfunction "2_2") (pintype "passive"))
      (node (ref "U1") (pin "16") (pinfunction "GND_16") (pintype "passive"))
      (node (ref "U100") (pin "1") (pinfunction "GND_1") (pintype "power_in"))
      (node (ref "U11") (pin "3") (pinfunction "E_3") (pintype "passive"))
      (node (ref "U12") (pin "3") (pinfunction "E_3") (pintype "passive"))
      (node (ref "U13") (pin "3") (pinfunction "E_3") (pintype "passive"))
      (node (ref "U14") (pin "3") (pinfunction "E_3") (pintype "passive"))
      (node (ref "U15") (pin "3") (pinfunction "E_3") (pintype "passive"))
      (node (ref "U16") (pin "3") (pinfunction "E_3") (pintype "passive"))
      (node (ref "U17") (pin "3") (pinfunction "E_3") (pintype "passive"))
      (node (ref "U18") (pin "3") (pinfunction "E_3") (pintype "passive"))
      (node (ref "U6") (pin "3") (pinfunction "GND_3") (pintype "output"))
      (node (ref "U6") (pin "5") (pinfunction "On/off_5") (pintype "output"))
      (node (ref "U6") (pin "6") (pinfunction "GND_6") (pintype "output"))
      (node (ref "USART") (pin "4") (pinfunction "4_4") (pintype "passive"))
      (node (ref "X0") (pin "2") (pinfunction "2_2") (pintype "passive"))
      (node (ref "X1") (pin "2") (pinfunction "2_2") (pintype "passive"))
      (node (ref "X2") (pin "2") (pinfunction "2_2") (pintype "passive"))
      (node (ref "X3") (pin "2") (pinfunction "2_2") (pintype "passive"))
      (node (ref "X4") (pin "2") (pinfunction "2_2") (pintype "passive"))
      (node (ref "X5") (pin "2") (pinfunction "2_2") (pintype "passive"))
      (node (ref "X6") (pin "2") (pinfunction "2_2") (pintype "passive"))
      (node (ref "X7") (pin "2") (pinfunction "2_2") (pintype "passive"))
    )
    (net (code "66") (name "MCUVCC") (class "Default")
      (node (ref "C1") (pin "1") (pinfunction "1_1") (pintype "passive"))
      (node (ref "SW") (pin "3") (pinfunction "3_3") (pintype "passive"))
      (node (ref "SW") (pin "6") (pinfunction "6_6") (pintype "passive"))
      (node (ref "U1") (pin "14") (pinfunction "VCC_14") (pintype "passive"))
    )
    (net (code "67") (name "Net-(ADC0-Pad1)") (class "Default")
      (node (ref "ADC0") (pin "1") (pinfunction "1_1") (pintype "passive"))
      (node (ref "R503") (pin "1") (pinfunction "1_1") (pintype "passive"))
    )
    (net (code "68") (name "Net-(ADC1-Pad1)") (class "Default")
      (node (ref "ADC1") (pin "1") (pinfunction "1_1") (pintype "passive"))
      (node (ref "R505") (pin "1") (pinfunction "1_1") (pintype "passive"))
    )
    (net (code "69") (name "Net-(ADC2-Pad1)") (class "Default")
      (node (ref "ADC2") (pin "1") (pinfunction "1_1") (pintype "passive"))
      (node (ref "R507") (pin "1") (pinfunction "1_1") (pintype "passive"))
    )
    (net (code "70") (name "Net-(ADC3-Pad1)") (class "Default")
      (node (ref "ADC3") (pin "1") (pinfunction "1_1") (pintype "passive"))
      (node (ref "R509") (pin "1") (pinfunction "1_1") (pintype "passive"))
    )
    (net (code "71") (name "Net-(ADC4-Pad1)") (class "Default")
      (node (ref "ADC4") (pin "1") (pinfunction "1_1") (pintype "passive"))
      (node (ref "R511") (pin "1") (pinfunction "1_1") (pintype "passive"))
    )
    (net (code "72") (name "Net-(ADC5-Pad1)") (class "Default")
      (node (ref "ADC5") (pin "1") (pinfunction "1_1") (pintype "passive"))
      (node (ref "R513") (pin "1") (pinfunction "1_1") (pintype "passive"))
    )
    (net (code "73") (name "Net-(ADC6-Pad1)") (class "Default")
      (node (ref "ADC6") (pin "1") (pinfunction "1_1") (pintype "passive"))
      (node (ref "R515") (pin "1") (pinfunction "1_1") (pintype "passive"))
    )
    (net (code "74") (name "Net-(ADC7-Pad1)") (class "Default")
      (node (ref "ADC7") (pin "1") (pinfunction "1_1") (pintype "passive"))
      (node (ref "R517") (pin "1") (pinfunction "1_1") (pintype "passive"))
    )
    (net (code "75") (name "Net-(D21-K)") (class "Default")
      (node (ref "D21") (pin "2") (pinfunction "K_2") (pintype "passive"))
      (node (ref "L10") (pin "1") (pinfunction "1_1") (pintype "passive"))
      (node (ref "U6") (pin "2") (pinfunction "Out_2") (pintype "output"))
    )
    (net (code "76") (name "Net-(LED20-K)") (class "Default")
      (node (ref "LED20") (pin "2") (pinfunction "K_2") (pintype "passive"))
      (node (ref "R10") (pin "2") (pinfunction "2_2") (pintype "passive"))
    )
    (net (code "77") (name "Net-(LED301-Pad1)") (class "Default")
      (node (ref "LED301") (pin "1") (pinfunction "1_1") (pintype "passive"))
      (node (ref "R301") (pin "1") (pinfunction "1_1") (pintype "passive"))
    )
    (net (code "78") (name "Net-(LED302-Pad1)") (class "Default")
      (node (ref "LED302") (pin "1") (pinfunction "1_1") (pintype "passive"))
      (node (ref "R302") (pin "1") (pinfunction "1_1") (pintype "passive"))
    )
    (net (code "79") (name "Net-(LED600-Pad1)") (class "Default")
      (node (ref "LED600") (pin "1") (pinfunction "1_1") (pintype "passive"))
      (node (ref "R11") (pin "1") (pinfunction "1_1") (pintype "passive"))
    )
    (net (code "80") (name "Net-(LED601-Pad1)") (class "Default")
      (node (ref "LED601") (pin "1") (pinfunction "1_1") (pintype "passive"))
      (node (ref "R12") (pin "1") (pinfunction "1_1") (pintype "passive"))
    )
    (net (code "81") (name "Net-(LED602-Pad1)") (class "Default")
      (node (ref "LED602") (pin "1") (pinfunction "1_1") (pintype "passive"))
      (node (ref "R13") (pin "1") (pinfunction "1_1") (pintype "passive"))
    )
    (net (code "82") (name "Net-(LED603-Pad1)") (class "Default")
      (node (ref "LED603") (pin "1") (pinfunction "1_1") (pintype "passive"))
      (node (ref "R14") (pin "1") (pinfunction "1_1") (pintype "passive"))
    )
    (net (code "83") (name "Net-(LED720-Pad1)") (class "Default")
      (node (ref "LED720") (pin "1") (pinfunction "1_1") (pintype "passive"))
      (node (ref "R720") (pin "2") (pinfunction "2_2") (pintype "passive"))
    )
    (net (code "84") (name "Net-(LED721-Pad1)") (class "Default")
      (node (ref "LED721") (pin "1") (pinfunction "1_1") (pintype "passive"))
      (node (ref "R721") (pin "2") (pinfunction "2_2") (pintype "passive"))
    )
    (net (code "85") (name "Net-(LED722-Pad1)") (class "Default")
      (node (ref "LED722") (pin "1") (pinfunction "1_1") (pintype "passive"))
      (node (ref "R722") (pin "2") (pinfunction "2_2") (pintype "passive"))
    )
    (net (code "86") (name "Net-(LED723-Pad1)") (class "Default")
      (node (ref "LED723") (pin "1") (pinfunction "1_1") (pintype "passive"))
      (node (ref "R723") (pin "2") (pinfunction "2_2") (pintype "passive"))
    )
    (net (code "87") (name "Net-(LED724-Pad1)") (class "Default")
      (node (ref "LED724") (pin "1") (pinfunction "1_1") (pintype "passive"))
      (node (ref "R724") (pin "2") (pinfunction "2_2") (pintype "passive"))
    )
    (net (code "88") (name "Net-(LED725-Pad1)") (class "Default")
      (node (ref "LED725") (pin "1") (pinfunction "1_1") (pintype "passive"))
      (node (ref "R725") (pin "2") (pinfunction "2_2") (pintype "passive"))
    )
    (net (code "89") (name "Net-(LED726-Pad1)") (class "Default")
      (node (ref "LED726") (pin "1") (pinfunction "1_1") (pintype "passive"))
      (node (ref "R726") (pin "2") (pinfunction "2_2") (pintype "passive"))
    )
    (net (code "90") (name "Net-(LED727-Pad1)") (class "Default")
      (node (ref "LED727") (pin "1") (pinfunction "1_1") (pintype "passive"))
      (node (ref "R727") (pin "2") (pinfunction "2_2") (pintype "passive"))
    )
    (net (code "91") (name "Net-(Q1-B)") (class "Default")
      (node (ref "Q1") (pin "1") (pinfunction "B_1") (pintype "passive"))
      (node (ref "Q2") (pin "3") (pinfunction "C_3") (pintype "passive"))
      (node (ref "R601") (pin "1") (pinfunction "1_1") (pintype "passive"))
    )
    (net (code "92") (name "Net-(Q1-C)") (class "Default")
      (node (ref "LED600") (pin "2") (pinfunction "2_2") (pintype "passive"))
      (node (ref "Q1") (pin "3") (pinfunction "C_3") (pintype "passive"))
      (node (ref "RELAY1") (pin "1") (pinfunction "1_1") (pintype "passive"))
    )
    (net (code "93") (name "Net-(Q3-B)") (class "Default")
      (node (ref "Q3") (pin "1") (pinfunction "B_1") (pintype "passive"))
      (node (ref "Q4") (pin "3") (pinfunction "C_3") (pintype "passive"))
      (node (ref "R602") (pin "2") (pinfunction "2_2") (pintype "passive"))
    )
    (net (code "94") (name "Net-(Q3-C)") (class "Default")
      (node (ref "LED601") (pin "2") (pinfunction "2_2") (pintype "passive"))
      (node (ref "Q3") (pin "3") (pinfunction "C_3") (pintype "passive"))
      (node (ref "RELAY2") (pin "1") (pinfunction "1_1") (pintype "passive"))
    )
    (net (code "95") (name "Net-(Q5-B)") (class "Default")
      (node (ref "Q5") (pin "1") (pinfunction "B_1") (pintype "passive"))
      (node (ref "Q6") (pin "3") (pinfunction "C_3") (pintype "passive"))
      (node (ref "R603") (pin "2") (pinfunction "2_2") (pintype "passive"))
    )
    (net (code "96") (name "Net-(Q5-C)") (class "Default")
      (node (ref "LED602") (pin "2") (pinfunction "2_2") (pintype "passive"))
      (node (ref "Q5") (pin "3") (pinfunction "C_3") (pintype "passive"))
      (node (ref "RELAY3") (pin "1") (pinfunction "1_1") (pintype "passive"))
    )
    (net (code "97") (name "Net-(Q7-B)") (class "Default")
      (node (ref "Q7") (pin "1") (pinfunction "B_1") (pintype "passive"))
      (node (ref "Q8") (pin "3") (pinfunction "C_3") (pintype "passive"))
      (node (ref "R604") (pin "2") (pinfunction "2_2") (pintype "passive"))
    )
    (net (code "98") (name "Net-(Q7-C)") (class "Default")
      (node (ref "LED603") (pin "2") (pinfunction "2_2") (pintype "passive"))
      (node (ref "Q7") (pin "3") (pinfunction "C_3") (pintype "passive"))
      (node (ref "RELAY4") (pin "1") (pinfunction "1_1") (pintype "passive"))
    )
    (net (code "99") (name "Net-(U11-A)") (class "Default")
      (node (ref "R701") (pin "2") (pinfunction "2_2") (pintype "passive"))
      (node (ref "U11") (pin "1") (pinfunction "A_1") (pintype "passive"))
    )
    (net (code "100") (name "Net-(U12-A)") (class "Default")
      (node (ref "R702") (pin "2") (pinfunction "2_2") (pintype "passive"))
      (node (ref "U12") (pin "1") (pinfunction "A_1") (pintype "passive"))
    )
    (net (code "101") (name "Net-(U13-A)") (class "Default")
      (node (ref "R703") (pin "2") (pinfunction "2_2") (pintype "passive"))
      (node (ref "U13") (pin "1") (pinfunction "A_1") (pintype "passive"))
    )
    (net (code "102") (name "Net-(U14-A)") (class "Default")
      (node (ref "R704") (pin "2") (pinfunction "2_2") (pintype "passive"))
      (node (ref "U14") (pin "1") (pinfunction "A_1") (pintype "passive"))
    )
    (net (code "103") (name "Net-(U15-A)") (class "Default")
      (node (ref "R705") (pin "2") (pinfunction "2_2") (pintype "passive"))
      (node (ref "U15") (pin "1") (pinfunction "A_1") (pintype "passive"))
    )
    (net (code "104") (name "Net-(U16-A)") (class "Default")
      (node (ref "R706") (pin "2") (pinfunction "2_2") (pintype "passive"))
      (node (ref "U16") (pin "1") (pinfunction "A_1") (pintype "passive"))
    )
    (net (code "105") (name "Net-(U17-A)") (class "Default")
      (node (ref "R707") (pin "2") (pinfunction "2_2") (pintype "passive"))
      (node (ref "U17") (pin "1") (pinfunction "A_1") (pintype "passive"))
    )
    (net (code "106") (name "Net-(U18-A)") (class "Default")
      (node (ref "R708") (pin "2") (pinfunction "2_2") (pintype "passive"))
      (node (ref "U18") (pin "1") (pinfunction "A_1") (pintype "passive"))
    )
    (net (code "107") (name "Net-(U100-V3)") (class "Default")
      (node (ref "C304") (pin "2") (pinfunction "2_2") (pintype "passive"))
      (node (ref "U100") (pin "4") (pinfunction "V3_4") (pintype "passive"))
    )
    (net (code "108") (name "Net-(U100-XI)") (class "Default")
      (node (ref "C301") (pin "1") (pinfunction "1_1") (pintype "passive"))
      (node (ref "U100") (pin "7") (pinfunction "XI_7") (pintype "passive"))
      (node (ref "Y20") (pin "1") (pinfunction "1_1") (pintype "passive"))
    )
    (net (code "109") (name "Net-(U100-XO)") (class "Default")
      (node (ref "C302") (pin "1") (pinfunction "1_1") (pintype "passive"))
      (node (ref "U100") (pin "8") (pinfunction "XO_8") (pintype "passive"))
      (node (ref "Y20") (pin "2") (pinfunction "2_2") (pintype "passive"))
    )
    (net (code "110") (name "POWER_OUT") (class "Default")
      (node (ref "C10") (pin "1") (pinfunction "1_1") (pintype "passive"))
      (node (ref "POWER") (pin "1") (pinfunction "1_1") (pintype "passive"))
      (node (ref "R701") (pin "1") (pinfunction "1_1") (pintype "passive"))
      (node (ref "R702") (pin "1") (pinfunction "1_1") (pintype "passive"))
      (node (ref "R703") (pin "1") (pinfunction "1_1") (pintype "passive"))
      (node (ref "R704") (pin "1") (pinfunction "1_1") (pintype "passive"))
      (node (ref "R705") (pin "1") (pinfunction "1_1") (pintype "passive"))
      (node (ref "R706") (pin "1") (pinfunction "1_1") (pintype "passive"))
      (node (ref "R707") (pin "1") (pinfunction "1_1") (pintype "passive"))
      (node (ref "R708") (pin "1") (pinfunction "1_1") (pintype "passive"))
      (node (ref "U6") (pin "1") (pinfunction "+VIN_1") (pintype "input"))
    )
    (net (code "111") (name "PVCC") (class "Default")
      (node (ref "C11") (pin "1") (pinfunction "1_1") (pintype "passive"))
      (node (ref "L10") (pin "2") (pinfunction "2_2") (pintype "passive"))
      (node (ref "S1") (pin "3") (pinfunction "3_3") (pintype "passive"))
      (node (ref "U6") (pin "4") (pinfunction "Feedback_4") (pintype "input"))
    )
    (net (code "112") (name "USB5V") (class "Default")
      (node (ref "S1") (pin "1") (pinfunction "1_1") (pintype "passive"))
      (node (ref "USART") (pin "1") (pinfunction "1_1") (pintype "passive"))
    )
    (net (code "113") (name "VCC") (class "Default")
      (node (ref "C303") (pin "1") (pinfunction "1_1") (pintype "passive"))
      (node (ref "LED20") (pin "1") (pinfunction "A_1") (pintype "passive"))
      (node (ref "P2") (pin "1") (pinfunction "1_1") (pintype "passive"))
      (node (ref "P3") (pin "1") (pinfunction "1_1") (pintype "passive"))
      (node (ref "P3") (pin "2") (pinfunction "2_2") (pintype "passive"))
      (node (ref "R11") (pin "2") (pinfunction "2_2") (pintype "passive"))
      (node (ref "R12") (pin "2") (pinfunction "2_2") (pintype "passive"))
      (node (ref "R13") (pin "2") (pinfunction "2_2") (pintype "passive"))
      (node (ref "R14") (pin "2") (pinfunction "2_2") (pintype "passive"))
      (node (ref "R26") (pin "2") (pinfunction "2_2") (pintype "passive"))
      (node (ref "R27") (pin "2") (pinfunction "2_2") (pintype "passive"))
      (node (ref "R301") (pin "2") (pinfunction "2_2") (pintype "passive"))
      (node (ref "R302") (pin "2") (pinfunction "2_2") (pintype "passive"))
      (node (ref "R45") (pin "2") (pinfunction "2_2") (pintype "passive"))
      (node (ref "R46") (pin "2") (pinfunction "2_2") (pintype "passive"))
      (node (ref "R601") (pin "2") (pinfunction "2_2") (pintype "passive"))
      (node (ref "R602") (pin "1") (pinfunction "1_1") (pintype "passive"))
      (node (ref "R603") (pin "1") (pinfunction "1_1") (pintype "passive"))
      (node (ref "R604") (pin "1") (pinfunction "1_1") (pintype "passive"))
      (node (ref "R720") (pin "1") (pinfunction "1_1") (pintype "passive"))
      (node (ref "R721") (pin "1") (pinfunction "1_1") (pintype "passive"))
      (node (ref "R722") (pin "1") (pinfunction "1_1") (pintype "passive"))
      (node (ref "R723") (pin "1") (pinfunction "1_1") (pintype "passive"))
      (node (ref "R724") (pin "1") (pinfunction "1_1") (pintype "passive"))
      (node (ref "R725") (pin "1") (pinfunction "1_1") (pintype "passive"))
      (node (ref "R726") (pin "1") (pinfunction "1_1") (pintype "passive"))
      (node (ref "R727") (pin "1") (pinfunction "1_1") (pintype "passive"))
      (node (ref "RELAY1") (pin "2") (pinfunction "2_2") (pintype "passive"))
      (node (ref "RELAY2") (pin "2") (pinfunction "2_2") (pintype "passive"))
      (node (ref "RELAY3") (pin "2") (pinfunction "2_2") (pintype "passive"))
      (node (ref "RELAY4") (pin "2") (pinfunction "2_2") (pintype "passive"))
      (node (ref "S1") (pin "2") (pinfunction "2_2") (pintype "passive"))
      (node (ref "SW") (pin "2") (pinfunction "2_2") (pintype "passive"))
      (node (ref "SW") (pin "5") (pinfunction "5_5") (pintype "passive"))
      (node (ref "U100") (pin "16") (pinfunction "VCC_16") (pintype "power_in"))
    )
    (net (code "114") (name "unconnected-(SW-Pad1)") (class "Default")
      (node (ref "SW") (pin "1") (pinfunction "1_1") (pintype "passive"))
    )
    (net (code "115") (name "unconnected-(SW-Pad4)") (class "Default")
      (node (ref "SW") (pin "4") (pinfunction "4_4") (pintype "passive"))
    )
    (net (code "116") (name "unconnected-(U100-CTS#-Pad9)") (class "Default")
      (node (ref "U100") (pin "9") (pinfunction "CTS#_9") (pintype "passive"))
    )
    (net (code "117") (name "unconnected-(U100-DCD#-Pad12)") (class "Default")
      (node (ref "U100") (pin "12") (pinfunction "DCD#_12") (pintype "passive"))
    )
    (net (code "118") (name "unconnected-(U100-DSR#-Pad10)") (class "Default")
      (node (ref "U100") (pin "10") (pinfunction "DSR#_10") (pintype "passive"))
    )
    (net (code "119") (name "unconnected-(U100-DTR#-Pad13)") (class "Default")
      (node (ref "U100") (pin "13") (pinfunction "DTR#_13") (pintype "passive"))
    )
    (net (code "120") (name "unconnected-(U100-RI#-Pad11)") (class "Default")
      (node (ref "U100") (pin "11") (pinfunction "RI#_11") (pintype "passive"))
    )
    (net (code "121") (name "unconnected-(U100-RS232-Pad15)") (class "Default")
      (node (ref "U100") (pin "15") (pinfunction "RS232_15") (pintype "passive"))
    )
    (net (code "122") (name "unconnected-(U100-RST#-Pad14)") (class "Default")
      (node (ref "U100") (pin "14") (pinfunction "RST#_14") (pintype "passive"))
    )
  )
)
